# endsem.net
KiCad netlist of a schematic drawn in EAGLE
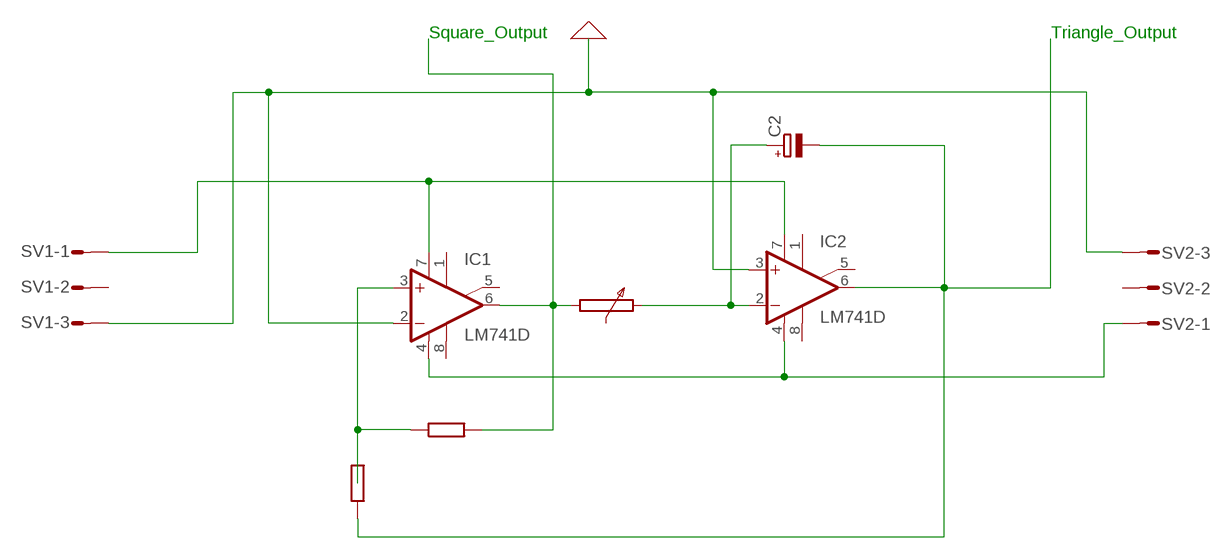
[diagram p0: schematic, sheet 1]

(export (version "E")
  (design (tool "Eeschema 10.0.6"))
  (components
    (comp (ref "C2")
      (value "CPOL-EUE5-6")
      (footprint "eagle-import:E5-6")
      (libsource (lib "eagle-import") (part "CPOL-EUE5-6"))
    )
    (comp (ref "IC1")
      (value "LM741D")
      (footprint "eagle-import:SO08")
      (libsource (lib "eagle-import") (part "741DLM"))
    )
    (comp (ref "IC2")
      (value "LM741D")
      (footprint "eagle-import:SO08")
      (libsource (lib "eagle-import") (part "741DLM"))
    )
    (comp (ref "SV1")
      (value "L03P")
      (footprint "eagle-import:L03P")
      (libsource (lib "eagle-import") (part "L03P"))
    )
    (comp (ref "SV2")
      (value "L03P")
      (footprint "eagle-import:L03P")
      (libsource (lib "eagle-import") (part "L03P"))
    )
  )
  (nets
    (net (code "1") (name "GND") (class "Default")
      (node (ref "IC1") (pin "2") (pinfunction "-IN_2") (pintype "input"))
      (node (ref "IC2") (pin "3") (pinfunction "+IN_3") (pintype "input"))
      (node (ref "SV1") (pin "3") (pinfunction "S_3") (pintype "passive"))
      (node (ref "SV2") (pin "3") (pinfunction "S_3") (pintype "passive"))
    )
    (net (code "2") (name "Net-(IC1-V+)") (class "Default")
      (node (ref "IC1") (pin "7") (pinfunction "V+_7") (pintype "power_in"))
      (node (ref "IC2") (pin "7") (pinfunction "V+_7") (pintype "power_in"))
      (node (ref "SV1") (pin "1") (pinfunction "S_1") (pintype "passive"))
    )
    (net (code "3") (name "Net-(IC1-V-)") (class "Default")
      (node (ref "IC1") (pin "4") (pinfunction "V-_4") (pintype "power_in"))
      (node (ref "IC2") (pin "4") (pinfunction "V-_4") (pintype "power_in"))
      (node (ref "SV2") (pin "1") (pinfunction "S_1") (pintype "passive"))
    )
    (net (code "4") (name "Net-(IC2--IN)") (class "Default")
      (node (ref "C2") (pin "+") (pinfunction "+_+") (pintype "passive"))
      (node (ref "IC2") (pin "2") (pinfunction "-IN_2") (pintype "input"))
    )
    (net (code "5") (name "Net-(IC2-OUT)") (class "Default")
      (node (ref "C2") (pin "-") (pinfunction "-_-") (pintype "passive"))
      (node (ref "IC2") (pin "6") (pinfunction "OUT_6") (pintype "output"))
    )
    (net (code "6") (name "unconnected-(IC1-+IN-Pad3)") (class "Default")
      (node (ref "IC1") (pin "3") (pinfunction "+IN_3") (pintype "input"))
    )
    (net (code "7") (name "unconnected-(IC1-ON1-Pad1)") (class "Default")
      (node (ref "IC1") (pin "1") (pinfunction "ON1_1") (pintype "passive"))
    )
    (net (code "8") (name "unconnected-(IC1-ON2-Pad5)") (class "Default")
      (node (ref "IC1") (pin "5") (pinfunction "ON2_5") (pintype "passive"))
    )
    (net (code "9") (name "unconnected-(IC1-OPT-Pad8)") (class "Default")
      (node (ref "IC1") (pin "8") (pinfunction "OPT_8") (pintype "passive"))
    )
    (net (code "10") (name "unconnected-(IC1-OUT-Pad6)") (class "Default")
      (node (ref "IC1") (pin "6") (pinfunction "OUT_6") (pintype "output"))
    )
    (net (code "11") (name "unconnected-(IC2-ON1-Pad1)") (class "Default")
      (node (ref "IC2") (pin "1") (pinfunction "ON1_1") (pintype "passive"))
    )
    (net (code "12") (name "unconnected-(IC2-ON2-Pad5)") (class "Default")
      (node (ref "IC2") (pin "5") (pinfunction "ON2_5") (pintype "passive"))
    )
    (net (code "13") (name "unconnected-(IC2-OPT-Pad8)") (class "Default")
      (node (ref "IC2") (pin "8") (pinfunction "OPT_8") (pintype "passive"))
    )
    (net (code "14") (name "unconnected-(SV1B-S-Pad2)") (class "Default")
      (node (ref "SV1") (pin "2") (pinfunction "S_2") (pintype "passive"))
    )
    (net (code "15") (name "unconnected-(SV2B-S-Pad2)") (class "Default")
      (node (ref "SV2") (pin "2") (pinfunction "S_2") (pintype "passive"))
    )
  )
)
